# F73-M-V1_0.net
KiCad netlist of a schematic drawn in Altium Designer
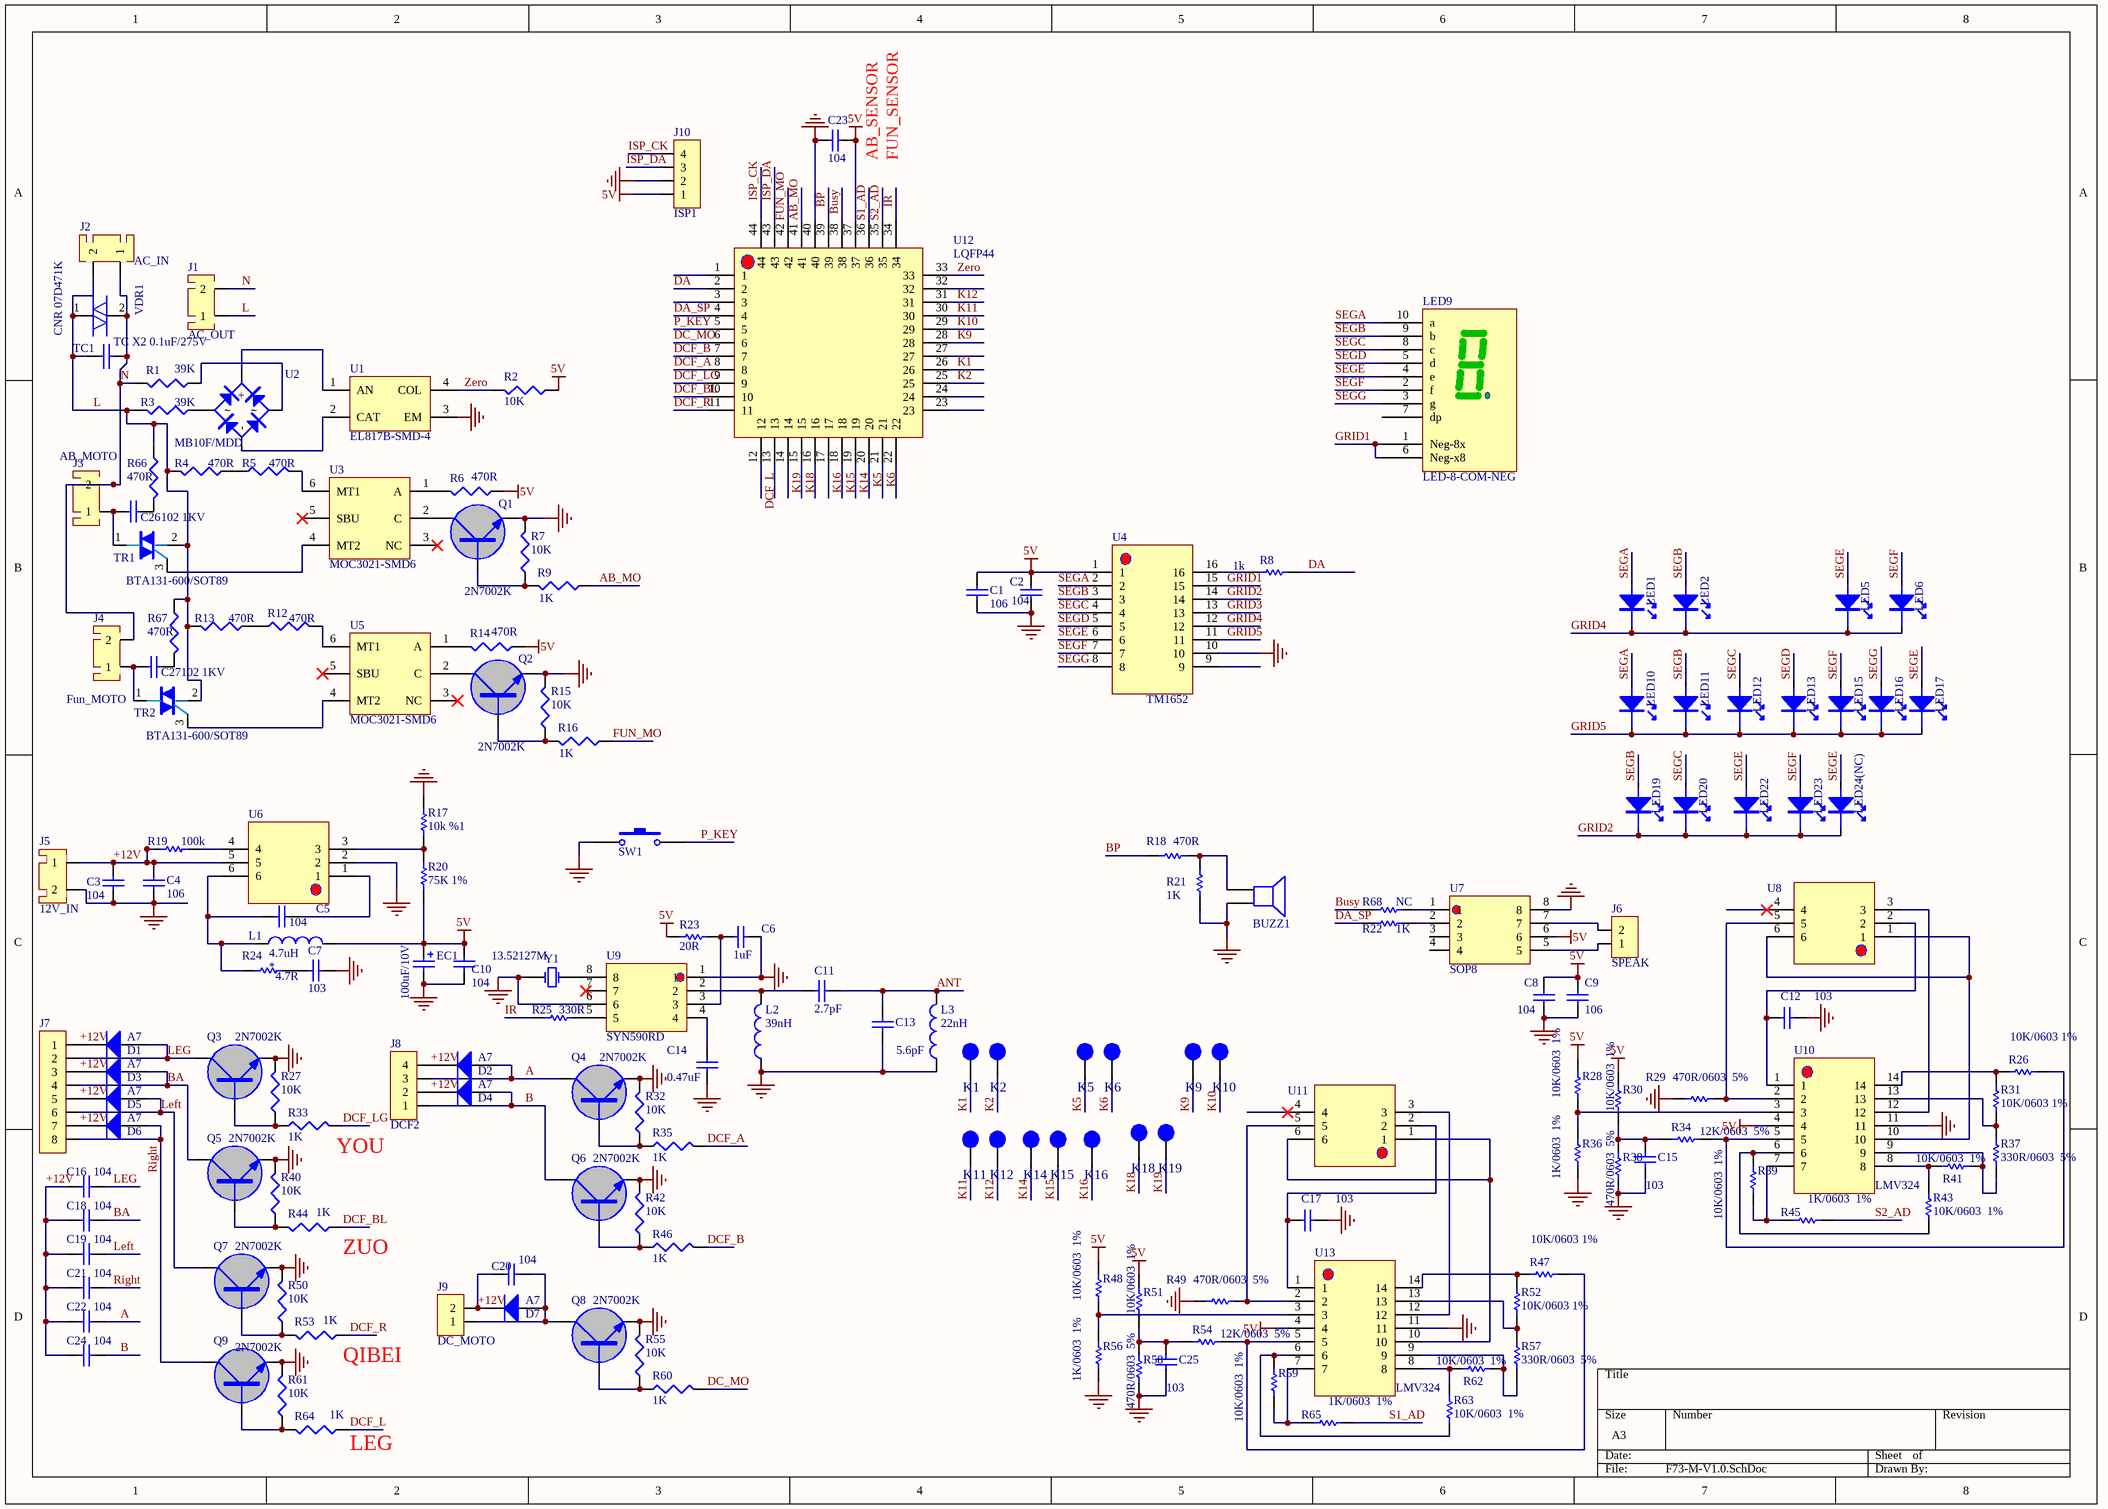
[diagram p0: F73-M-V1.0.SchDoc]

(export (version "E")
  (design (tool "Eeschema 10.0.6"))
  (components
    (comp (ref "BUZZ1")
      (value "Speaker")
      (footprint "BUZ-1407-7.5")
      (description "Loudspeaker")
      (fields (field (name "MANUFACTURER") "Generic Components"))
      (libsource (lib "Miscellaneous Devices") (part "Speaker"))
    )
    (comp (ref "C1")
      (value "106")
      (footprint "0805C")
      (description "Capacitor")
      (fields
        (field (name "MANUFACTURER") "Generic Components")
        (field (name "PUBLISHER") "Altium Hobart Technology Centre")
      )
      (libsource (lib "Miscellaneous Devices") (part "Cap"))
    )
    (comp (ref "C2")
      (value "104")
      (footprint "0603C")
      (description "Capacitor")
      (fields
        (field (name "MANUFACTURER") "Generic Components")
        (field (name "PUBLISHER") "Altium Hobart Technology Centre")
      )
      (libsource (lib "Miscellaneous Devices") (part "Cap"))
    )
    (comp (ref "C3")
      (value "104")
      (footprint "0603C")
      (description "Capacitor")
      (fields (field (name "PUBLISHER") "Altium Limited"))
      (libsource (lib "Phil") (part "Cap"))
    )
    (comp (ref "C4")
      (value "106")
      (footprint "0805C")
      (description "Capacitor")
      (fields
        (field (name "MANUFACTURER") "Generic Components")
        (field (name "PUBLISHER") "Altium Hobart Technology Centre")
      )
      (libsource (lib "Miscellaneous Devices") (part "Cap"))
    )
    (comp (ref "C5")
      (value "104")
      (footprint "0603C")
      (description "Capacitor")
      (fields
        (field (name "MANUFACTURER") "Generic Components")
        (field (name "PUBLISHER") "Altium Hobart Technology Centre")
      )
      (libsource (lib "Miscellaneous Devices") (part "Cap"))
    )
    (comp (ref "C6")
      (value "1uF")
      (footprint "0603C")
      (description "Capacitor")
      (fields (field (name "PUBLISHER") "Altium Limited"))
      (libsource (lib "Phil") (part "Cap"))
    )
    (comp (ref "C7")
      (value "103")
      (footprint "0603C")
      (description "Capacitor")
      (fields (field (name "PUBLISHER") "Altium Limited"))
      (libsource (lib "Phil") (part "Cap"))
    )
    (comp (ref "C8")
      (value "104")
      (footprint "0603C")
      (description "Capacitor")
      (fields
        (field (name "MANUFACTURER") "Generic Components")
        (field (name "PUBLISHER") "Altium Hobart Technology Centre")
      )
      (libsource (lib "Miscellaneous Devices") (part "Cap"))
    )
    (comp (ref "C9")
      (value "106")
      (footprint "0805C")
      (description "Capacitor")
      (fields
        (field (name "MANUFACTURER") "Generic Components")
        (field (name "PUBLISHER") "Altium Hobart Technology Centre")
      )
      (libsource (lib "Miscellaneous Devices") (part "Cap"))
    )
    (comp (ref "C10")
      (value "104")
      (footprint "0603C")
      (description "Capacitor")
      (fields
        (field (name "MANUFACTURER") "Generic Components")
        (field (name "PUBLISHER") "Altium Hobart Technology Centre")
      )
      (libsource (lib "Miscellaneous Devices") (part "Cap"))
    )
    (comp (ref "C11")
      (value "2.7pF")
      (footprint "0603C")
      (description "Capacitor")
      (fields (field (name "PUBLISHER") "Altium Limited"))
      (libsource (lib "Phil") (part "Cap"))
    )
    (comp (ref "C12")
      (value "103")
      (footprint "0603C")
      (description "Capacitor")
      (fields (field (name "PUBLISHER") "Altium Limited"))
      (libsource (lib "Phil") (part "Cap"))
    )
    (comp (ref "C13")
      (value "5.6pF")
      (footprint "0603C")
      (description "Capacitor")
      (fields (field (name "PUBLISHER") "Altium Limited"))
      (libsource (lib "Phil") (part "Cap"))
    )
    (comp (ref "C14")
      (value "0.47uF")
      (footprint "0603C")
      (description "Capacitor")
      (fields (field (name "PUBLISHER") "Altium Limited"))
      (libsource (lib "Phil") (part "Cap"))
    )
    (comp (ref "C15")
      (value "103")
      (footprint "0603C")
      (description "Capacitor")
      (fields (field (name "PUBLISHER") "Altium Limited"))
      (libsource (lib "Phil") (part "Cap"))
    )
    (comp (ref "C16")
      (value "104")
      (footprint "0603C")
      (description "Capacitor")
      (fields (field (name "PUBLISHER") "Altium Limited"))
      (libsource (lib "Phil") (part "Cap"))
    )
    (comp (ref "C17")
      (value "103")
      (footprint "0603C")
      (description "Capacitor")
      (fields (field (name "PUBLISHER") "Altium Limited"))
      (libsource (lib "Phil") (part "Cap"))
    )
    (comp (ref "C18")
      (value "104")
      (footprint "0603C")
      (description "Capacitor")
      (fields (field (name "PUBLISHER") "Altium Limited"))
      (libsource (lib "Phil") (part "Cap"))
    )
    (comp (ref "C19")
      (value "104")
      (footprint "0603C")
      (description "Capacitor")
      (fields (field (name "PUBLISHER") "Altium Limited"))
      (libsource (lib "Phil") (part "Cap"))
    )
    (comp (ref "C20")
      (value "104")
      (footprint "0603C")
      (description "Capacitor")
      (fields
        (field (name "MANUFACTURER") "Generic Components")
        (field (name "PUBLISHER") "Altium Hobart Technology Centre")
      )
      (libsource (lib "Miscellaneous Devices") (part "Cap"))
    )
    (comp (ref "C21")
      (value "104")
      (footprint "0603C")
      (description "Capacitor")
      (fields (field (name "PUBLISHER") "Altium Limited"))
      (libsource (lib "Phil") (part "Cap"))
    )
    (comp (ref "C22")
      (value "104")
      (footprint "0603C")
      (description "Capacitor")
      (fields (field (name "PUBLISHER") "Altium Limited"))
      (libsource (lib "Phil") (part "Cap"))
    )
    (comp (ref "C23")
      (value "104")
      (footprint "0603C")
      (description "Capacitor")
      (fields (field (name "PUBLISHER") "Altium Limited"))
      (libsource (lib "HF-FOUR-M-1.0") (part "Cap"))
    )
    (comp (ref "C24")
      (value "104")
      (footprint "0603C")
      (description "Capacitor")
      (fields (field (name "PUBLISHER") "Altium Limited"))
      (libsource (lib "Phil") (part "Cap"))
    )
    (comp (ref "C25")
      (value "103")
      (footprint "0603C")
      (description "Capacitor")
      (fields (field (name "PUBLISHER") "Altium Limited"))
      (libsource (lib "Phil") (part "Cap"))
    )
    (comp (ref "C26")
      (value "102 1KV")
      (footprint "1206C")
      (description "Capacitor")
      (fields
        (field (name "MANUFACTURER") "Generic Components")
        (field (name "PUBLISHER") "Altium Hobart Technology Centre")
      )
      (libsource (lib "Miscellaneous Devices") (part "Cap"))
    )
    (comp (ref "C27")
      (value "102 1KV")
      (footprint "1206C")
      (description "Capacitor")
      (fields
        (field (name "MANUFACTURER") "Generic Components")
        (field (name "PUBLISHER") "Altium Hobart Technology Centre")
      )
      (libsource (lib "Miscellaneous Devices") (part "Cap"))
    )
    (comp (ref "D1")
      (value "A7")
      (footprint "SOD-123FL_L2.8-W1.8-LS3.7")
      (description "1 Amp General Purpose Rectifier")
      (fields (field (name "PUBLISHER") "Altium Limited"))
      (libsource (lib "Phil") (part "Diode 1N4007"))
    )
    (comp (ref "D2")
      (value "A7")
      (footprint "SOD-123FL_L2.8-W1.8-LS3.7")
      (description "1 Amp General Purpose Rectifier")
      (fields (field (name "PUBLISHER") "Altium Limited"))
      (libsource (lib "Phil") (part "Diode 1N4007"))
    )
    (comp (ref "D3")
      (value "A7")
      (footprint "SOD-123FL_L2.8-W1.8-LS3.7")
      (description "1 Amp General Purpose Rectifier")
      (fields (field (name "PUBLISHER") "Altium Limited"))
      (libsource (lib "Phil") (part "Diode 1N4007"))
    )
    (comp (ref "D4")
      (value "A7")
      (footprint "SOD-123FL_L2.8-W1.8-LS3.7")
      (description "1 Amp General Purpose Rectifier")
      (fields (field (name "PUBLISHER") "Altium Limited"))
      (libsource (lib "Phil") (part "Diode 1N4007"))
    )
    (comp (ref "D5")
      (value "A7")
      (footprint "SOD-123FL_L2.8-W1.8-LS3.7")
      (description "1 Amp General Purpose Rectifier")
      (fields (field (name "PUBLISHER") "Altium Limited"))
      (libsource (lib "Phil") (part "Diode 1N4007"))
    )
    (comp (ref "D6")
      (value "A7")
      (footprint "SOD-123FL_L2.8-W1.8-LS3.7")
      (description "1 Amp General Purpose Rectifier")
      (fields (field (name "PUBLISHER") "Altium Limited"))
      (libsource (lib "Phil") (part "Diode 1N4007"))
    )
    (comp (ref "D7")
      (value "A7")
      (footprint "SOD-123FL_L2.8-W1.8-LS3.7")
      (description "1 Amp General Purpose Rectifier")
      (fields (field (name "PUBLISHER") "Altium Limited"))
      (libsource (lib "Phil") (part "Diode 1N4007"))
    )
    (comp (ref "EC1")
      (value "100uF/10V")
      (footprint "CAP SMD 6.3*5.5mm")
      (description "Polarized Capacitor (Radial)")
      (fields
        (field (name "MANUFACTURER") "Generic Components")
        (field (name "PUBLISHER") "Altium Hobart Technology Centre")
      )
      (libsource (lib "Miscellaneous Devices") (part "Cap Pol1"))
    )
    (comp (ref "J1")
      (value "AC_OUT")
      (footprint "K-VH3.96-3P")
      (libsource (lib "SCH Connector(2019-4-13)") (part "PITCH3.96-5.0-2A"))
    )
    (comp (ref "J2")
      (value "AC_IN")
      (footprint "K-VH3.96-3P")
      (libsource (lib "") (part "PITCH3.96-5.0-2A_1"))
    )
    (comp (ref "J3")
      (value "AB_MOTO")
      (footprint "K-VH3.96-3P")
      (libsource (lib "SCH Connector(2019-4-13)") (part "PITCH3.96-5.0-2A"))
    )
    (comp (ref "J4")
      (value "Fun_MOTO")
      (footprint "K-VH3.96-3P")
      (libsource (lib "SCH Connector(2019-4-13)") (part "PITCH3.96-5.0-2A"))
    )
    (comp (ref "J5")
      (value "12V_IN")
      (footprint "CON2-SMD-XHB 2*2.5MM")
      (libsource (lib "SCH Connector(2019-4-13)") (part "PITCH2.5-2A"))
    )
    (comp (ref "J6")
      (value "SPEAK")
      (footprint "CON2-SMD_PH2.0-1X2PW")
      (libsource (lib "Phil") (part "CON2"))
    )
    (comp (ref "J7")
      (value "~")
      (footprint "CON8-SMD-XHB 8*2.5MM")
      (libsource (lib "HF-FOUR-M-1.0") (part "CON8"))
    )
    (comp (ref "J8")
      (value "DCF2")
      (footprint "CON4-SMD_4P-P2.54_XH2.54-4AB")
      (libsource (lib "") (part "CON4_1"))
    )
    (comp (ref "J9")
      (value "DC_MOTO")
      (footprint "CON2-SMD-XHB 2*2.5MM")
      (libsource (lib "") (part "CON2_1"))
    )
    (comp (ref "J10") (value "ISP1") (footprint "CON4 -2.54-H") (libsource (lib "Phil") (part "CON4")))
    (comp (ref "K1")
      (value "Φ15 H8mm弹簧")
      (footprint "TK_HF-13*13*8")
      (libsource (lib "HF-FOUR-M-1.0") (part "TOUCH-PAD"))
    )
    (comp (ref "K2")
      (value "Φ15 H8mm弹簧")
      (footprint "TK_HF-13*13*8")
      (libsource (lib "HF-FOUR-M-1.0") (part "TOUCH-PAD"))
    )
    (comp (ref "K5")
      (value "Φ15 H8mm弹簧")
      (footprint "TK_HF-13*13*8")
      (libsource (lib "HF-FOUR-M-1.0") (part "TOUCH-PAD"))
    )
    (comp (ref "K6")
      (value "Φ15 H8mm弹簧")
      (footprint "TK_HF-13*13*8")
      (libsource (lib "HF-FOUR-M-1.0") (part "TOUCH-PAD"))
    )
    (comp (ref "K9")
      (value "Φ15 H8mm弹簧")
      (footprint "TK_HF-13*13*8")
      (libsource (lib "HF-FOUR-M-1.0") (part "TOUCH-PAD"))
    )
    (comp (ref "K10")
      (value "Φ15 H8mm弹簧")
      (footprint "TK_HF-13*13*8")
      (libsource (lib "HF-FOUR-M-1.0") (part "TOUCH-PAD"))
    )
    (comp (ref "K11")
      (value "Φ15 H8mm弹簧")
      (footprint "TK_HF-13*13*8")
      (libsource (lib "HF-FOUR-M-1.0") (part "TOUCH-PAD"))
    )
    (comp (ref "K12")
      (value "Φ15 H8mm弹簧")
      (footprint "TK_HF-13*13*8")
      (libsource (lib "HF-FOUR-M-1.0") (part "TOUCH-PAD"))
    )
    (comp (ref "K14")
      (value "Φ15 H8mm弹簧")
      (footprint "TK_HF-13*13*8")
      (libsource (lib "HF-FOUR-M-1.0") (part "TOUCH-PAD"))
    )
    (comp (ref "K15")
      (value "Φ15 H8mm弹簧")
      (footprint "TK_HF-13*13*8")
      (libsource (lib "HF-FOUR-M-1.0") (part "TOUCH-PAD"))
    )
    (comp (ref "K16")
      (value "Φ15 H8mm弹簧")
      (footprint "TK_HF-13*13*8")
      (libsource (lib "HF-FOUR-M-1.0") (part "TOUCH-PAD"))
    )
    (comp (ref "K18")
      (value "Φ15 H8mm弹簧")
      (footprint "TK_HF-13*13*8")
      (libsource (lib "HF-FOUR-M-1.0") (part "TOUCH-PAD"))
    )
    (comp (ref "K19")
      (value "Φ15 H8mm弹簧")
      (footprint "TK_HF-13*13*8")
      (libsource (lib "HF-FOUR-M-1.0") (part "TOUCH-PAD"))
    )
    (comp (ref "L1")
      (value "4.7uH")
      (footprint "INDC5050")
      (description "Inductor")
      (fields (field (name "ALTIUM_VALUE") "*") (field (name "PUBLISHER") "Altium Limited"))
      (libsource (lib "Phil") (part "Inductor"))
    )
    (comp (ref "L2")
      (value "39nH")
      (footprint "0603R")
      (description "Inductor")
      (fields (field (name "PUBLISHER") "Altium Limited"))
      (libsource (lib "Phil") (part "Inductor"))
    )
    (comp (ref "L3")
      (value "22nH")
      (footprint "0603R")
      (description "Inductor")
      (fields (field (name "PUBLISHER") "Altium Limited"))
      (libsource (lib "Phil") (part "Inductor"))
    )
    (comp (ref "LED1") (value "LED_0603") (footprint "LED_0603") (libsource (lib "Phil") (part "LED")))
    (comp (ref "LED2") (value "LED_0603") (footprint "LED_0603") (libsource (lib "Phil") (part "LED")))
    (comp (ref "LED5") (value "LED_0603") (footprint "LED_0603") (libsource (lib "Phil") (part "LED")))
    (comp (ref "LED6") (value "LED_0603") (footprint "LED_0603") (libsource (lib "Phil") (part "LED")))
    (comp (ref "LED9")
      (value "LED-8-COM-NEG")
      (footprint "LED1B-10P(7.5*14*H8.5 P2.54*10.16)")
      (libsource (lib "F73-M-V1.0") (part "LED-8-COM-NEG"))
    )
    (comp (ref "LED10") (value "LED_0603") (footprint "LED_0603") (libsource (lib "Phil") (part "LED")))
    (comp (ref "LED11") (value "LED_0603") (footprint "LED_0603") (libsource (lib "Phil") (part "LED")))
    (comp (ref "LED12") (value "LED_0603") (footprint "LED_0603") (libsource (lib "Phil") (part "LED")))
    (comp (ref "LED13") (value "LED_0603") (footprint "LED_0603") (libsource (lib "Phil") (part "LED")))
    (comp (ref "LED15") (value "LED_0603") (footprint "LED_0603") (libsource (lib "Phil") (part "LED")))
    (comp (ref "LED16") (value "LED_0603") (footprint "LED_0603") (libsource (lib "Phil") (part "LED")))
    (comp (ref "LED17") (value "LED_0603") (footprint "LED_0603") (libsource (lib "Phil") (part "LED")))
    (comp (ref "LED19") (value "LED_0603") (footprint "LED_0603") (libsource (lib "Phil") (part "LED")))
    (comp (ref "LED20") (value "LED_0603") (footprint "LED_0603") (libsource (lib "Phil") (part "LED")))
    (comp (ref "LED22") (value "LED_0603") (footprint "LED_0603") (libsource (lib "Phil") (part "LED")))
    (comp (ref "LED23") (value "LED_0603") (footprint "LED_0603") (libsource (lib "Phil") (part "LED")))
    (comp (ref "LED24(NC)") (value "LED_0603") (footprint "LED_0603") (libsource (lib "Phil") (part "LED")))
    (comp (ref "Q1")
      (value "2N7002K")
      (footprint "SOT-23 - MOS")
      (libsource (lib "SCH-Transistor-Triac-Mosfet(2018-9-19-1)") (part "NPN-8050-BCE-25V/500mA"))
    )
    (comp (ref "Q2")
      (value "2N7002K")
      (footprint "SOT-23 - MOS")
      (libsource (lib "SCH-Transistor-Triac-Mosfet(2018-9-19-1)") (part "NPN-8050-BCE-25V/500mA"))
    )
    (comp (ref "Q3")
      (value "2N7002K")
      (footprint "SOT-23 - MOS")
      (libsource (lib "SCH-Transistor-Triac-Mosfet(2018-9-19-1)") (part "NPN-8050-BCE-25V/500mA"))
    )
    (comp (ref "Q4")
      (value "2N7002K")
      (footprint "SOT-23 - MOS")
      (libsource (lib "SCH-Transistor-Triac-Mosfet(2018-9-19-1)") (part "NPN-8050-BCE-25V/500mA"))
    )
    (comp (ref "Q5")
      (value "2N7002K")
      (footprint "SOT-23 - MOS")
      (libsource (lib "SCH-Transistor-Triac-Mosfet(2018-9-19-1)") (part "NPN-8050-BCE-25V/500mA"))
    )
    (comp (ref "Q6")
      (value "2N7002K")
      (footprint "SOT-23 - MOS")
      (libsource (lib "SCH-Transistor-Triac-Mosfet(2018-9-19-1)") (part "NPN-8050-BCE-25V/500mA"))
    )
    (comp (ref "Q7")
      (value "2N7002K")
      (footprint "SOT-23 - MOS")
      (libsource (lib "SCH-Transistor-Triac-Mosfet(2018-9-19-1)") (part "NPN-8050-BCE-25V/500mA"))
    )
    (comp (ref "Q8")
      (value "2N7002K")
      (footprint "SOT-23 - MOS")
      (libsource (lib "SCH-Transistor-Triac-Mosfet(2018-9-19-1)") (part "NPN-8050-BCE-25V/500mA"))
    )
    (comp (ref "Q9")
      (value "2N7002K")
      (footprint "SOT-23 - MOS")
      (libsource (lib "SCH-Transistor-Triac-Mosfet(2018-9-19-1)") (part "NPN-8050-BCE-25V/500mA"))
    )
    (comp (ref "R1")
      (value "39K")
      (footprint "1206R")
      (libsource (lib "SCH Resistor(2019-6-10)") (part "1Ω±1%/0805-1206"))
    )
    (comp (ref "R2")
      (value "10K")
      (footprint "0603")
      (libsource (lib "SCH Resistor(2019-6-10)") (part "1Ω±1%/0603-0805"))
    )
    (comp (ref "R3")
      (value "39K")
      (footprint "1206R")
      (libsource (lib "SCH Resistor(2019-6-10)") (part "1Ω±1%/0805-1206"))
    )
    (comp (ref "R4")
      (value "470R")
      (footprint "1206R")
      (libsource (lib "SCH Resistor(2019-6-10)") (part "1Ω±1%/0805-1206"))
    )
    (comp (ref "R5")
      (value "470R")
      (footprint "1206R")
      (libsource (lib "SCH Resistor(2019-6-10)") (part "1Ω±1%/0805-1206"))
    )
    (comp (ref "R6")
      (value "470R")
      (footprint "0603")
      (libsource (lib "SCH Resistor(2019-6-10)") (part "1Ω±1%/0603-0805"))
    )
    (comp (ref "R7")
      (value "10K")
      (footprint "0603")
      (libsource (lib "SCH Resistor(2019-6-10)") (part "1Ω±1%/0603-0805"))
    )
    (comp (ref "R8")
      (value "1k")
      (footprint "0603R")
      (description "Resistor")
      (fields (field (name "PUBLISHER") "Altium Limited"))
      (libsource (lib "Phil") (part "Res1"))
    )
    (comp (ref "R9")
      (value "1K")
      (footprint "0603")
      (libsource (lib "SCH Resistor(2019-6-10)") (part "1Ω±1%/0603-0805"))
    )
    (comp (ref "R12")
      (value "470R")
      (footprint "1206R")
      (libsource (lib "SCH Resistor(2019-6-10)") (part "1Ω±1%/0805-1206"))
    )
    (comp (ref "R13")
      (value "470R")
      (footprint "1206R")
      (libsource (lib "SCH Resistor(2019-6-10)") (part "1Ω±1%/0805-1206"))
    )
    (comp (ref "R14")
      (value "470R")
      (footprint "0603")
      (libsource (lib "SCH Resistor(2019-6-10)") (part "1Ω±1%/0603-0805"))
    )
    (comp (ref "R15")
      (value "10K")
      (footprint "0603")
      (libsource (lib "SCH Resistor(2019-6-10)") (part "1Ω±1%/0603-0805"))
    )
    (comp (ref "R16")
      (value "1K")
      (footprint "0603")
      (libsource (lib "SCH Resistor(2019-6-10)") (part "1Ω±1%/0603-0805"))
    )
    (comp (ref "R17")
      (value "10k %1")
      (footprint "0603R")
      (description "Resistor")
      (fields (field (name "PUBLISHER") "Altium Limited"))
      (libsource (lib "Phil") (part "Res1"))
    )
    (comp (ref "R18")
      (value "470R")
      (footprint "0603R")
      (description "Resistor")
      (fields (field (name "PUBLISHER") "Altium Limited"))
      (libsource (lib "Phil") (part "Res1"))
    )
    (comp (ref "R19")
      (value "100k")
      (footprint "0603R")
      (description "Resistor")
      (fields (field (name "PUBLISHER") "Altium Limited"))
      (libsource (lib "Phil") (part "Res1"))
    )
    (comp (ref "R20")
      (value "75K 1%")
      (footprint "0603R")
      (description "Resistor")
      (fields (field (name "PUBLISHER") "Altium Limited"))
      (libsource (lib "Phil") (part "Res1"))
    )
    (comp (ref "R21")
      (value "1K")
      (footprint "0603R")
      (description "Resistor")
      (fields (field (name "PUBLISHER") "Altium Limited"))
      (libsource (lib "Phil") (part "Res1"))
    )
    (comp (ref "R22")
      (value "1K")
      (footprint "0603R")
      (description "Resistor")
      (fields (field (name "PUBLISHER") "Altium Limited"))
      (libsource (lib "Phil") (part "Res1"))
    )
    (comp (ref "R23")
      (value "20R")
      (footprint "0603R")
      (description "Resistor")
      (fields (field (name "PUBLISHER") "Altium Limited"))
      (libsource (lib "Phil") (part "Res1"))
    )
    (comp (ref "R24")
      (value "4.7R")
      (footprint "0603R")
      (description "Resistor")
      (fields (field (name "PUBLISHER") "Altium Limited"))
      (libsource (lib "Phil") (part "Res1"))
    )
    (comp (ref "R25")
      (value "330R")
      (footprint "0603R")
      (description "Resistor")
      (fields (field (name "PUBLISHER") "Altium Limited"))
      (libsource (lib "Phil") (part "Res1"))
    )
    (comp (ref "R26")
      (value "10K/0603 1%")
      (footprint "0603R")
      (description "Resistor")
      (fields (field (name "PUBLISHER") "Altium Limited"))
      (libsource (lib "Phil") (part "Res1"))
    )
    (comp (ref "R27")
      (value "10K")
      (footprint "0603")
      (libsource (lib "SCH Resistor(2019-6-10)") (part "1Ω±1%/0603-0805"))
    )
    (comp (ref "R28")
      (value "10K/0603  1%")
      (footprint "0603R")
      (description "Resistor")
      (fields (field (name "PUBLISHER") "Altium Limited"))
      (libsource (lib "Phil") (part "Res1"))
    )
    (comp (ref "R29")
      (value "470R/0603  5%")
      (footprint "0603R")
      (description "Resistor")
      (fields (field (name "PUBLISHER") "Altium Limited"))
      (libsource (lib "Phil") (part "Res1"))
    )
    (comp (ref "R30")
      (value "10K/0603  1%")
      (footprint "0603R")
      (description "Resistor")
      (fields (field (name "PUBLISHER") "Altium Limited"))
      (libsource (lib "Phil") (part "Res1"))
    )
    (comp (ref "R31")
      (value "10K/0603 1%")
      (footprint "0603R")
      (description "Resistor")
      (fields (field (name "PUBLISHER") "Altium Limited"))
      (libsource (lib "Phil") (part "Res1"))
    )
    (comp (ref "R32")
      (value "10K")
      (footprint "0603")
      (libsource (lib "SCH Resistor(2019-6-10)") (part "1Ω±1%/0603-0805"))
    )
    (comp (ref "R33")
      (value "1K")
      (footprint "0603")
      (libsource (lib "SCH Resistor(2019-6-10)") (part "1Ω±1%/0603-0805"))
    )
    (comp (ref "R34")
      (value "12K/0603  5%")
      (footprint "0603R")
      (description "Resistor")
      (fields (field (name "PUBLISHER") "Altium Limited"))
      (libsource (lib "Phil") (part "Res1"))
    )
    (comp (ref "R35")
      (value "1K")
      (footprint "0603")
      (libsource (lib "SCH Resistor(2019-6-10)") (part "1Ω±1%/0603-0805"))
    )
    (comp (ref "R36")
      (value "1K/0603  1%")
      (footprint "0603R")
      (description "Resistor")
      (fields (field (name "PUBLISHER") "Altium Limited"))
      (libsource (lib "Phil") (part "Res1"))
    )
    (comp (ref "R37")
      (value "330R/0603  5%")
      (footprint "0603R")
      (description "Resistor")
      (fields (field (name "PUBLISHER") "Altium Limited"))
      (libsource (lib "Phil") (part "Res1"))
    )
    (comp (ref "R38")
      (value "470R/0603  5%")
      (footprint "0603R")
      (description "Resistor")
      (fields (field (name "PUBLISHER") "Altium Limited"))
      (libsource (lib "Phil") (part "Res1"))
    )
    (comp (ref "R39")
      (value "10K/0603  1%")
      (footprint "0603R")
      (description "Resistor")
      (fields (field (name "PUBLISHER") "Altium Limited"))
      (libsource (lib "Phil") (part "Res1"))
    )
    (comp (ref "R40")
      (value "10K")
      (footprint "0603")
      (libsource (lib "SCH Resistor(2019-6-10)") (part "1Ω±1%/0603-0805"))
    )
    (comp (ref "R41")
      (value "10K/0603  1%")
      (footprint "0603R")
      (description "Resistor")
      (fields (field (name "PUBLISHER") "Altium Limited"))
      (libsource (lib "Phil") (part "Res1"))
    )
    (comp (ref "R42")
      (value "10K")
      (footprint "0603")
      (libsource (lib "SCH Resistor(2019-6-10)") (part "1Ω±1%/0603-0805"))
    )
    (comp (ref "R43")
      (value "10K/0603  1%")
      (footprint "0603R")
      (description "Resistor")
      (fields (field (name "PUBLISHER") "Altium Limited"))
      (libsource (lib "Phil") (part "Res1"))
    )
    (comp (ref "R44")
      (value "1K")
      (footprint "0603")
      (libsource (lib "SCH Resistor(2019-6-10)") (part "1Ω±1%/0603-0805"))
    )
    (comp (ref "R45")
      (value "1K/0603  1%")
      (footprint "0603R")
      (description "Resistor")
      (fields (field (name "PUBLISHER") "Altium Limited"))
      (libsource (lib "Phil") (part "Res1"))
    )
    (comp (ref "R46")
      (value "1K")
      (footprint "0603")
      (libsource (lib "SCH Resistor(2019-6-10)") (part "1Ω±1%/0603-0805"))
    )
    (comp (ref "R47")
      (value "10K/0603 1%")
      (footprint "0603R")
      (description "Resistor")
      (fields (field (name "PUBLISHER") "Altium Limited"))
      (libsource (lib "Phil") (part "Res1"))
    )
    (comp (ref "R48")
      (value "10K/0603  1%")
      (footprint "0603R")
      (description "Resistor")
      (fields (field (name "PUBLISHER") "Altium Limited"))
      (libsource (lib "Phil") (part "Res1"))
    )
    (comp (ref "R49")
      (value "470R/0603  5%")
      (footprint "0603R")
      (description "Resistor")
      (fields (field (name "PUBLISHER") "Altium Limited"))
      (libsource (lib "Phil") (part "Res1"))
    )
    (comp (ref "R50")
      (value "10K")
      (footprint "0603")
      (libsource (lib "SCH Resistor(2019-6-10)") (part "1Ω±1%/0603-0805"))
    )
    (comp (ref "R51")
      (value "10K/0603  1%")
      (footprint "0603R")
      (description "Resistor")
      (fields (field (name "PUBLISHER") "Altium Limited"))
      (libsource (lib "Phil") (part "Res1"))
    )
    (comp (ref "R52")
      (value "10K/0603 1%")
      (footprint "0603R")
      (description "Resistor")
      (fields (field (name "PUBLISHER") "Altium Limited"))
      (libsource (lib "Phil") (part "Res1"))
    )
    (comp (ref "R53")
      (value "1K")
      (footprint "0603")
      (libsource (lib "SCH Resistor(2019-6-10)") (part "1Ω±1%/0603-0805"))
    )
    (comp (ref "R54")
      (value "12K/0603  5%")
      (footprint "0603R")
      (description "Resistor")
      (fields (field (name "PUBLISHER") "Altium Limited"))
      (libsource (lib "Phil") (part "Res1"))
    )
    (comp (ref "R55")
      (value "10K")
      (footprint "0603")
      (libsource (lib "SCH Resistor(2019-6-10)") (part "1Ω±1%/0603-0805"))
    )
    (comp (ref "R56")
      (value "1K/0603  1%")
      (footprint "0603R")
      (description "Resistor")
      (fields (field (name "PUBLISHER") "Altium Limited"))
      (libsource (lib "Phil") (part "Res1"))
    )
    (comp (ref "R57")
      (value "330R/0603  5%")
      (footprint "0603R")
      (description "Resistor")
      (fields (field (name "PUBLISHER") "Altium Limited"))
      (libsource (lib "Phil") (part "Res1"))
    )
    (comp (ref "R58")
      (value "470R/0603  5%")
      (footprint "0603R")
      (description "Resistor")
      (fields (field (name "PUBLISHER") "Altium Limited"))
      (libsource (lib "Phil") (part "Res1"))
    )
    (comp (ref "R59")
      (value "10K/0603  1%")
      (footprint "0603R")
      (description "Resistor")
      (fields (field (name "PUBLISHER") "Altium Limited"))
      (libsource (lib "Phil") (part "Res1"))
    )
    (comp (ref "R60")
      (value "1K")
      (footprint "0603")
      (libsource (lib "SCH Resistor(2019-6-10)") (part "1Ω±1%/0603-0805"))
    )
    (comp (ref "R61")
      (value "10K")
      (footprint "0603")
      (libsource (lib "SCH Resistor(2019-6-10)") (part "1Ω±1%/0603-0805"))
    )
    (comp (ref "R62")
      (value "10K/0603  1%")
      (footprint "0603R")
      (description "Resistor")
      (fields (field (name "PUBLISHER") "Altium Limited"))
      (libsource (lib "Phil") (part "Res1"))
    )
    (comp (ref "R63")
      (value "10K/0603  1%")
      (footprint "0603R")
      (description "Resistor")
      (fields (field (name "PUBLISHER") "Altium Limited"))
      (libsource (lib "Phil") (part "Res1"))
    )
    (comp (ref "R64")
      (value "1K")
      (footprint "0603")
      (libsource (lib "SCH Resistor(2019-6-10)") (part "1Ω±1%/0603-0805"))
    )
    (comp (ref "R65")
      (value "1K/0603  1%")
      (footprint "0603R")
      (description "Resistor")
      (fields (field (name "PUBLISHER") "Altium Limited"))
      (libsource (lib "Phil") (part "Res1"))
    )
    (comp (ref "R66")
      (value "470R")
      (footprint "1206R")
      (libsource (lib "SCH Resistor(2019-6-10)") (part "1Ω±1%/0805-1206"))
    )
    (comp (ref "R67")
      (value "470R")
      (footprint "1206R")
      (libsource (lib "SCH Resistor(2019-6-10)") (part "1Ω±1%/0805-1206"))
    )
    (comp (ref "R68")
      (value "NC")
      (footprint "0603R")
      (description "Resistor")
      (fields (field (name "PUBLISHER") "Altium Limited"))
      (libsource (lib "Phil") (part "Res1"))
    )
    (comp (ref "SW1")
      (value "SW-PB")
      (footprint "BUTTON-SMD-6*6*10")
      (description "Switch")
      (fields (field (name "PUBLISHER") "Altium Limited"))
      (libsource (lib "Phil") (part "SW-PB"))
    )
    (comp (ref "TC1")
      (value "TC X2 0.1uF/275V")
      (footprint "CAP-TH_L13.0-W6.0-P10.00-D0.6")
      (libsource (lib "TEL SCH") (part "CAP1"))
    )
    (comp (ref "TR1")
      (value "BTA131-600/SOT89")
      (footprint "SOT-89 BT131-600")
      (libsource (lib "TEL SCH") (part "Triac"))
    )
    (comp (ref "TR2")
      (value "BTA131-600/SOT89")
      (footprint "SOT-89 BT131-600")
      (libsource (lib "TEL SCH") (part "Triac"))
    )
    (comp (ref "U1")
      (value "EL817B-SMD-4")
      (footprint "PC817-smd")
      (libsource (lib "SCH IC-Power(2019-2-14)") (part "EL817-DIP-4"))
    )
    (comp (ref "U2")
      (value "MB10F/MDD")
      (footprint "DB-MB10F")
      (description "Diode Bridge")
      (libsource (lib "SCH Diode-Bridge-Zener(2018-10-15)") (part "BD-ABS10/MB10S"))
    )
    (comp (ref "U3")
      (value "MOC3021-SMD6")
      (footprint "SMD6")
      (libsource (lib "SCH IC-Power(2019-2-14)") (part "MOC3021-DIP-6"))
    )
    (comp (ref "U4") (value "TM1652") (footprint "SOP16(150MIL)") (libsource (lib "Phil") (part "SOP16")))
    (comp (ref "U5")
      (value "MOC3021-SMD6")
      (footprint "SMD6")
      (libsource (lib "SCH IC-Power(2019-2-14)") (part "MOC3021-DIP-6"))
    )
    (comp (ref "U6") (value "HT7712") (footprint "SOT23-6_M") (libsource (lib "Phil") (part "SOP6")))
    (comp (ref "U7") (value "SOP8") (footprint "SOP8-SS") (libsource (lib "") (part "SOP8_1")))
    (comp (ref "U8") (value "SOP6") (footprint "PSG010R/S") (libsource (lib "Phil") (part "SOP6")))
    (comp (ref "U9") (value "SYN590RD") (footprint "SOP8(5.1*6.2mm)") (libsource (lib "Phil") (part "SOP8")))
    (comp (ref "U10") (value "LMV324") (footprint "SOP14(150mil)") (libsource (lib "Phil") (part "SOP14")))
    (comp (ref "U11") (value "SOP6") (footprint "PSG010R/S") (libsource (lib "Phil") (part "SOP6")))
    (comp (ref "U12") (value "LQFP44") (footprint "LQFP44") (libsource (lib "Phil") (part "LQFP44")))
    (comp (ref "U13") (value "LMV324") (footprint "SOP14(150mil)") (libsource (lib "Phil") (part "SOP14")))
    (comp (ref "VDR1")
      (value "CNR 07D471K")
      (footprint "RES-TH_L9.0-W5.0-P5-D0.7-S3.00")
      (libsource (lib "LZB_SCH") (part "VAR"))
    )
    (comp (ref "Y1")
      (value "13.52127M")
      (footprint "HC-49S_L11.4-W4.8")
      (description "Crystal Oscillator")
      (fields (field (name "PUBLISHER") "Altium Limited"))
      (libsource (lib "Phil") (part "XTAL"))
    )
  )
  (nets
    (net (code "1") (name "/+12V") (class "Default")
      (node (ref "C16") (pin "1") (pinfunction "1_1") (pintype "passive"))
      (node (ref "C18") (pin "1") (pinfunction "1_1") (pintype "passive"))
      (node (ref "C19") (pin "1") (pinfunction "1_1") (pintype "passive"))
      (node (ref "C20") (pin "1") (pinfunction "1_1") (pintype "passive"))
      (node (ref "C21") (pin "1") (pinfunction "1_1") (pintype "passive"))
      (node (ref "C22") (pin "1") (pinfunction "1_1") (pintype "passive"))
      (node (ref "C24") (pin "1") (pinfunction "1_1") (pintype "passive"))
      (node (ref "C3") (pin "1") (pinfunction "1_1") (pintype "passive"))
      (node (ref "C4") (pin "1") (pinfunction "1_1") (pintype "passive"))
      (node (ref "D1") (pin "2") (pinfunction "K_2") (pintype "passive"))
      (node (ref "D2") (pin "2") (pinfunction "K_2") (pintype "passive"))
      (node (ref "D3") (pin "2") (pinfunction "K_2") (pintype "passive"))
      (node (ref "D4") (pin "2") (pinfunction "K_2") (pintype "passive"))
      (node (ref "D5") (pin "2") (pinfunction "K_2") (pintype "passive"))
      (node (ref "D6") (pin "2") (pinfunction "K_2") (pintype "passive"))
      (node (ref "D7") (pin "2") (pinfunction "K_2") (pintype "passive"))
      (node (ref "J5") (pin "1") (pinfunction "1_1") (pintype "passive"))
      (node (ref "J7") (pin "1") (pinfunction "1_1") (pintype "passive"))
      (node (ref "J7") (pin "3") (pinfunction "3_3") (pintype "passive"))
      (node (ref "J7") (pin "5") (pinfunction "5_5") (pintype "passive"))
      (node (ref "J7") (pin "7") (pinfunction "7_7") (pintype "passive"))
      (node (ref "J8") (pin "2") (pinfunction "2_2") (pintype "passive"))
      (node (ref "J8") (pin "4") (pinfunction "4_4") (pintype "passive"))
      (node (ref "J9") (pin "2") (pinfunction "2_2") (pintype "passive"))
      (node (ref "R19") (pin "1") (pinfunction "1_1") (pintype "passive"))
      (node (ref "U6") (pin "5") (pinfunction "5_5") (pintype "passive"))
    )
    (net (code "2") (name "/A") (class "Default")
      (node (ref "C22") (pin "2") (pinfunction "2_2") (pintype "passive"))
      (node (ref "D2") (pin "1") (pinfunction "A_1") (pintype "passive"))
      (node (ref "J8") (pin "3") (pinfunction "3_3") (pintype "passive"))
      (node (ref "Q4") (pin "C") (pinfunction "C_C") (pintype "passive"))
    )
    (net (code "3") (name "/AB_MO") (class "Default")
      (node (ref "R9") (pin "1") (pintype "passive"))
      (node (ref "U12") (pin "41") (pinfunction "41_41") (pintype "passive"))
    )
    (net (code "4") (name "/ANT") (class "Default")
      (node (ref "C11") (pin "1") (pinfunction "1_1") (pintype "passive"))
      (node (ref "C13") (pin "2") (pinfunction "2_2") (pintype "passive"))
      (node (ref "L3") (pin "2") (pinfunction "2_2") (pintype "passive"))
    )
    (net (code "5") (name "/B") (class "Default")
      (node (ref "C24") (pin "2") (pinfunction "2_2") (pintype "passive"))
      (node (ref "D4") (pin "1") (pinfunction "A_1") (pintype "passive"))
      (node (ref "J8") (pin "1") (pinfunction "1_1") (pintype "passive"))
      (node (ref "Q6") (pin "C") (pinfunction "C_C") (pintype "passive"))
    )
    (net (code "6") (name "/BA") (class "Default")
      (node (ref "C18") (pin "2") (pinfunction "2_2") (pintype "passive"))
      (node (ref "D3") (pin "1") (pinfunction "A_1") (pintype "passive"))
      (node (ref "J7") (pin "4") (pinfunction "4_4") (pintype "passive"))
      (node (ref "Q5") (pin "C") (pinfunction "C_C") (pintype "passive"))
    )
    (net (code "7") (name "/BP") (class "Default")
      (node (ref "R18") (pin "2") (pinfunction "2_2") (pintype "passive"))
      (node (ref "U12") (pin "39") (pinfunction "39_39") (pintype "passive"))
    )
    (net (code "8") (name "/Busy") (class "Default")
      (node (ref "R68") (pin "1") (pinfunction "1_1") (pintype "passive"))
      (node (ref "U12") (pin "38") (pinfunction "38_38") (pintype "passive"))
    )
    (net (code "9") (name "/DA") (class "Default")
      (node (ref "R8") (pin "1") (pinfunction "1_1") (pintype "passive"))
      (node (ref "U12") (pin "2") (pinfunction "2_2") (pintype "passive"))
    )
    (net (code "10") (name "/DA_SP") (class "Default")
      (node (ref "R22") (pin "1") (pinfunction "1_1") (pintype "passive"))
      (node (ref "U12") (pin "4") (pinfunction "4_4") (pintype "passive"))
    )
    (net (code "11") (name "/DCF_A") (class "Default")
      (node (ref "R35") (pin "2") (pintype "passive"))
      (node (ref "U12") (pin "8") (pinfunction "8_8") (pintype "passive"))
    )
    (net (code "12") (name "/DCF_B") (class "Default")
      (node (ref "R46") (pin "2") (pintype "passive"))
      (node (ref "U12") (pin "7") (pinfunction "7_7") (pintype "passive"))
    )
    (net (code "13") (name "/DCF_BL") (class "Default")
      (node (ref "R44") (pin "1") (pintype "passive"))
      (node (ref "U12") (pin "10") (pinfunction "10_10") (pintype "passive"))
    )
    (net (code "14") (name "/DCF_L") (class "Default")
      (node (ref "R64") (pin "1") (pintype "passive"))
      (node (ref "U12") (pin "12") (pinfunction "12_12") (pintype "passive"))
    )
    (net (code "15") (name "/DCF_LG") (class "Default")
      (node (ref "R33") (pin "2") (pintype "passive"))
      (node (ref "U12") (pin "9") (pinfunction "9_9") (pintype "passive"))
    )
    (net (code "16") (name "/DCF_R") (class "Default")
      (node (ref "R53") (pin "1") (pintype "passive"))
      (node (ref "U12") (pin "11") (pinfunction "11_11") (pintype "passive"))
    )
    (net (code "17") (name "/DC_MO") (class "Default")
      (node (ref "R60") (pin "2") (pintype "passive"))
      (node (ref "U12") (pin "6") (pinfunction "6_6") (pintype "passive"))
    )
    (net (code "18") (name "/FUN_MO") (class "Default")
      (node (ref "R16") (pin "1") (pintype "passive"))
      (node (ref "U12") (pin "42") (pinfunction "42_42") (pintype "passive"))
    )
    (net (code "19") (name "/GRID1") (class "Default")
      (node (ref "LED9") (pin "1") (pinfunction "Neg-8x_1") (pintype "passive"))
      (node (ref "LED9") (pin "6") (pinfunction "Neg-x8_6") (pintype "passive"))
      (node (ref "U4") (pin "15") (pinfunction "15_15") (pintype "passive"))
    )
    (net (code "20") (name "/GRID2") (class "Default")
      (node (ref "LED19") (pin "2") (pinfunction "2_2") (pintype "passive"))
      (node (ref "LED20") (pin "2") (pinfunction "2_2") (pintype "passive"))
      (node (ref "LED22") (pin "2") (pinfunction "2_2") (pintype "passive"))
      (node (ref "LED23") (pin "2") (pinfunction "2_2") (pintype "passive"))
      (node (ref "LED24(NC)") (pin "2") (pinfunction "2_2") (pintype "passive"))
      (node (ref "U4") (pin "14") (pinfunction "14_14") (pintype "passive"))
    )
    (net (code "21") (name "/GRID3") (class "Default")
      (node (ref "U4") (pin "13") (pinfunction "13_13") (pintype "passive"))
    )
    (net (code "22") (name "/GRID4") (class "Default")
      (node (ref "LED1") (pin "2") (pinfunction "2_2") (pintype "passive"))
      (node (ref "LED2") (pin "2") (pinfunction "2_2") (pintype "passive"))
      (node (ref "LED5") (pin "2") (pinfunction "2_2") (pintype "passive"))
      (node (ref "LED6") (pin "2") (pinfunction "2_2") (pintype "passive"))
      (node (ref "U4") (pin "12") (pinfunction "12_12") (pintype "passive"))
    )
    (net (code "23") (name "/GRID5") (class "Default")
      (node (ref "LED10") (pin "2") (pinfunction "2_2") (pintype "passive"))
      (node (ref "LED11") (pin "2") (pinfunction "2_2") (pintype "passive"))
      (node (ref "LED12") (pin "2") (pinfunction "2_2") (pintype "passive"))
      (node (ref "LED13") (pin "2") (pinfunction "2_2") (pintype "passive"))
      (node (ref "LED15") (pin "2") (pinfunction "2_2") (pintype "passive"))
      (node (ref "LED16") (pin "2") (pinfunction "2_2") (pintype "passive"))
      (node (ref "LED17") (pin "2") (pinfunction "2_2") (pintype "passive"))
      (node (ref "U4") (pin "11") (pinfunction "11_11") (pintype "passive"))
    )
    (net (code "24") (name "/IR") (class "Default")
      (node (ref "R25") (pin "1") (pinfunction "1_1") (pintype "passive"))
      (node (ref "U12") (pin "34") (pinfunction "34_34") (pintype "passive"))
    )
    (net (code "25") (name "/ISP_CK") (class "Default")
      (node (ref "J10") (pin "4") (pinfunction "4_4") (pintype "passive"))
      (node (ref "U12") (pin "44") (pinfunction "44_44") (pintype "passive"))
    )
    (net (code "26") (name "/ISP_DA") (class "Default")
      (node (ref "J10") (pin "3") (pinfunction "3_3") (pintype "passive"))
      (node (ref "U12") (pin "43") (pinfunction "43_43") (pintype "passive"))
    )
    (net (code "27") (name "/K1") (class "Default")
      (node (ref "K1") (pin "2") (pinfunction "2_2") (pintype "passive"))
      (node (ref "U12") (pin "26") (pinfunction "26_26") (pintype "passive"))
    )
    (net (code "28") (name "/K2") (class "Default")
      (node (ref "K2") (pin "2") (pinfunction "2_2") (pintype "passive"))
      (node (ref "U12") (pin "25") (pinfunction "25_25") (pintype "passive"))
    )
    (net (code "29") (name "/K5") (class "Default")
      (node (ref "K5") (pin "2") (pinfunction "2_2") (pintype "passive"))
      (node (ref "U12") (pin "20") (pinfunction "20_20") (pintype "passive"))
    )
    (net (code "30") (name "/K6") (class "Default")
      (node (ref "K6") (pin "2") (pinfunction "2_2") (pintype "passive"))
      (node (ref "U12") (pin "21") (pinfunction "21_21") (pintype "passive"))
    )
    (net (code "31") (name "/K9") (class "Default")
      (node (ref "K9") (pin "2") (pinfunction "2_2") (pintype "passive"))
      (node (ref "U12") (pin "28") (pinfunction "28_28") (pintype "passive"))
    )
    (net (code "32") (name "/K10") (class "Default")
      (node (ref "K10") (pin "2") (pinfunction "2_2") (pintype "passive"))
      (node (ref "U12") (pin "29") (pinfunction "29_29") (pintype "passive"))
    )
    (net (code "33") (name "/K11") (class "Default")
      (node (ref "K11") (pin "2") (pinfunction "2_2") (pintype "passive"))
      (node (ref "U12") (pin "30") (pinfunction "30_30") (pintype "passive"))
    )
    (net (code "34") (name "/K12") (class "Default")
      (node (ref "K12") (pin "2") (pinfunction "2_2") (pintype "passive"))
      (node (ref "U12") (pin "31") (pinfunction "31_31") (pintype "passive"))
    )
    (net (code "35") (name "/K14") (class "Default")
      (node (ref "K14") (pin "2") (pinfunction "2_2") (pintype "passive"))
      (node (ref "U12") (pin "19") (pinfunction "19_19") (pintype "passive"))
    )
    (net (code "36") (name "/K15") (class "Default")
      (node (ref "K15") (pin "2") (pinfunction "2_2") (pintype "passive"))
      (node (ref "U12") (pin "18") (pinfunction "18_18") (pintype "passive"))
    )
    (net (code "37") (name "/K16") (class "Default")
      (node (ref "K16") (pin "2") (pinfunction "2_2") (pintype "passive"))
      (node (ref "U12") (pin "17") (pinfunction "17_17") (pintype "passive"))
    )
    (net (code "38") (name "/K18") (class "Default")
      (node (ref "K18") (pin "2") (pinfunction "2_2") (pintype "passive"))
      (node (ref "U12") (pin "15") (pinfunction "15_15") (pintype "passive"))
    )
    (net (code "39") (name "/K19") (class "Default")
      (node (ref "K19") (pin "2") (pinfunction "2_2") (pintype "passive"))
      (node (ref "U12") (pin "14") (pinfunction "14_14") (pintype "passive"))
    )
    (net (code "40") (name "/L") (class "Default")
      (node (ref "J1") (pin "1") (pinfunction "1_1") (pintype "passive"))
      (node (ref "J2") (pin "2") (pinfunction "2_2") (pintype "passive"))
      (node (ref "R13") (pin "2") (pintype "passive"))
      (node (ref "R3") (pin "2") (pintype "passive"))
      (node (ref "R4") (pin "2") (pintype "passive"))
      (node (ref "R66") (pin "1") (pintype "passive"))
      (node (ref "R67") (pin "1") (pintype "passive"))
      (node (ref "TC1") (pin "2") (pintype "passive"))
      (node (ref "TR1") (pin "2") (pintype "passive"))
      (node (ref "TR2") (pin "2") (pintype "passive"))
      (node (ref "VDR1") (pin "1") (pinfunction "1_1") (pintype "passive"))
    )
    (net (code "41") (name "/LEG") (class "Default")
      (node (ref "C16") (pin "2") (pinfunction "2_2") (pintype "passive"))
      (node (ref "D1") (pin "1") (pinfunction "A_1") (pintype "passive"))
      (node (ref "J7") (pin "2") (pinfunction "2_2") (pintype "passive"))
      (node (ref "Q3") (pin "C") (pinfunction "C_C") (pintype "passive"))
    )
    (net (code "42") (name "/Left") (class "Default")
      (node (ref "C19") (pin "2") (pinfunction "2_2") (pintype "passive"))
      (node (ref "D5") (pin "1") (pinfunction "A_1") (pintype "passive"))
      (node (ref "J7") (pin "6") (pinfunction "6_6") (pintype "passive"))
      (node (ref "Q7") (pin "C") (pinfunction "C_C") (pintype "passive"))
    )
    (net (code "43") (name "/N") (class "Default")
      (node (ref "J1") (pin "2") (pinfunction "2_2") (pintype "passive"))
      (node (ref "J2") (pin "1") (pinfunction "1_1") (pintype "passive"))
      (node (ref "J3") (pin "2") (pinfunction "2_2") (pintype "passive"))
      (node (ref "J4") (pin "2") (pinfunction "2_2") (pintype "passive"))
      (node (ref "R1") (pin "2") (pintype "passive"))
      (node (ref "TC1") (pin "1") (pintype "passive"))
      (node (ref "VDR1") (pin "2") (pinfunction "2_2") (pintype "passive"))
    )
    (net (code "44") (name "/P_KEY") (class "Default")
      (node (ref "SW1") (pin "2") (pinfunction "2_2") (pintype "passive"))
      (node (ref "U12") (pin "5") (pinfunction "5_5") (pintype "passive"))
    )
    (net (code "45") (name "/Right") (class "Default")
      (node (ref "C21") (pin "2") (pinfunction "2_2") (pintype "passive"))
      (node (ref "D6") (pin "1") (pinfunction "A_1") (pintype "passive"))
      (node (ref "J7") (pin "8") (pinfunction "8_8") (pintype "passive"))
      (node (ref "Q9") (pin "C") (pinfunction "C_C") (pintype "passive"))
    )
    (net (code "46") (name "/S1_AD") (class "Default")
      (node (ref "R65") (pin "1") (pinfunction "1_1") (pintype "passive"))
      (node (ref "U12") (pin "36") (pinfunction "36_36") (pintype "passive"))
    )
    (net (code "47") (name "/S2_AD") (class "Default")
      (node (ref "R45") (pin "1") (pinfunction "1_1") (pintype "passive"))
      (node (ref "U12") (pin "35") (pinfunction "35_35") (pintype "passive"))
    )
    (net (code "48") (name "/SEGA") (class "Default")
      (node (ref "LED1") (pin "1") (pinfunction "1_1") (pintype "passive"))
      (node (ref "LED10") (pin "1") (pinfunction "1_1") (pintype "passive"))
      (node (ref "LED9") (pin "10") (pinfunction "a_10") (pintype "passive"))
      (node (ref "U4") (pin "2") (pinfunction "2_2") (pintype "passive"))
    )
    (net (code "49") (name "/SEGB") (class "Default")
      (node (ref "LED11") (pin "1") (pinfunction "1_1") (pintype "passive"))
      (node (ref "LED19") (pin "1") (pinfunction "1_1") (pintype "passive"))
      (node (ref "LED2") (pin "1") (pinfunction "1_1") (pintype "passive"))
      (node (ref "LED9") (pin "9") (pinfunction "b_9") (pintype "passive"))
      (node (ref "U4") (pin "3") (pinfunction "3_3") (pintype "passive"))
    )
    (net (code "50") (name "/SEGC") (class "Default")
      (node (ref "LED12") (pin "1") (pinfunction "1_1") (pintype "passive"))
      (node (ref "LED20") (pin "1") (pinfunction "1_1") (pintype "passive"))
      (node (ref "LED9") (pin "8") (pinfunction "c_8") (pintype "passive"))
      (node (ref "U4") (pin "4") (pinfunction "4_4") (pintype "passive"))
    )
    (net (code "51") (name "/SEGD") (class "Default")
      (node (ref "LED13") (pin "1") (pinfunction "1_1") (pintype "passive"))
      (node (ref "LED9") (pin "5") (pinfunction "d_5") (pintype "passive"))
      (node (ref "U4") (pin "5") (pinfunction "5_5") (pintype "passive"))
    )
    (net (code "52") (name "/SEGE") (class "Default")
      (node (ref "LED17") (pin "1") (pinfunction "1_1") (pintype "passive"))
      (node (ref "LED22") (pin "1") (pinfunction "1_1") (pintype "passive"))
      (node (ref "LED24(NC)") (pin "1") (pinfunction "1_1") (pintype "passive"))
      (node (ref "LED5") (pin "1") (pinfunction "1_1") (pintype "passive"))
      (node (ref "LED9") (pin "4") (pinfunction "e_4") (pintype "passive"))
      (node (ref "U4") (pin "6") (pinfunction "6_6") (pintype "passive"))
    )
    (net (code "53") (name "/SEGF") (class "Default")
      (node (ref "LED15") (pin "1") (pinfunction "1_1") (pintype "passive"))
      (node (ref "LED23") (pin "1") (pinfunction "1_1") (pintype "passive"))
      (node (ref "LED6") (pin "1") (pinfunction "1_1") (pintype "passive"))
      (node (ref "LED9") (pin "2") (pinfunction "f_2") (pintype "passive"))
      (node (ref "U4") (pin "7") (pinfunction "7_7") (pintype "passive"))
    )
    (net (code "54") (name "/SEGG") (class "Default")
      (node (ref "LED16") (pin "1") (pinfunction "1_1") (pintype "passive"))
      (node (ref "LED9") (pin "3") (pinfunction "g_3") (pintype "passive"))
      (node (ref "U4") (pin "8") (pinfunction "8_8") (pintype "passive"))
    )
    (net (code "55") (name "/Zero") (class "Default")
      (node (ref "R2") (pin "2") (pintype "passive"))
      (node (ref "U1") (pin "4") (pinfunction "COL_4") (pintype "passive"))
      (node (ref "U12") (pin "33") (pinfunction "33_33") (pintype "passive"))
    )
    (net (code "56") (name "5V") (class "Default")
      (node (ref "C1") (pin "2") (pinfunction "2_2") (pintype "passive"))
      (node (ref "C10") (pin "1") (pinfunction "1_1") (pintype "passive"))
      (node (ref "C2") (pin "2") (pinfunction "2_2") (pintype "passive"))
      (node (ref "C23") (pin "1") (pinfunction "1_1") (pintype "passive"))
      (node (ref "C8") (pin "1") (pinfunction "1_1") (pintype "passive"))
      (node (ref "C9") (pin "1") (pinfunction "1_1") (pintype "passive"))
      (node (ref "EC1") (pin "1") (pinfunction "1_1") (pintype "passive"))
      (node (ref "J10") (pin "1") (pinfunction "1_1") (pintype "passive"))
      (node (ref "L1") (pin "2") (pinfunction "2_2") (pintype "passive"))
      (node (ref "R14") (pin "1") (pintype "passive"))
      (node (ref "R2") (pin "1") (pintype "passive"))
      (node (ref "R20") (pin "1") (pinfunction "1_1") (pintype "passive"))
      (node (ref "R23") (pin "1") (pinfunction "1_1") (pintype "passive"))
      (node (ref "R28") (pin "1") (pinfunction "1_1") (pintype "passive"))
      (node (ref "R30") (pin "1") (pinfunction "1_1") (pintype "passive"))
      (node (ref "R48") (pin "1") (pinfunction "1_1") (pintype "passive"))
      (node (ref "R51") (pin "1") (pinfunction "1_1") (pintype "passive"))
      (node (ref "R6") (pin "1") (pintype "passive"))
      (node (ref "U10") (pin "4") (pinfunction "4_4") (pintype "passive"))
      (node (ref "U12") (pin "37") (pinfunction "37_37") (pintype "passive"))
      (node (ref "U13") (pin "4") (pinfunction "4_4") (pintype "passive"))
      (node (ref "U4") (pin "1") (pinfunction "1_1") (pintype "passive"))
      (node (ref "U7") (pin "6") (pinfunction "6_6") (pintype "passive"))
    )
    (net (code "57") (name "GND") (class "Default")
      (node (ref "BUZZ1") (pin "1") (pinfunction "1_1") (pintype "passive"))
      (node (ref "C1") (pin "1") (pinfunction "1_1") (pintype "passive"))
      (node (ref "C10") (pin "2") (pinfunction "2_2") (pintype "passive"))
      (node (ref "C12") (pin "1") (pinfunction "1_1") (pintype "passive"))
      (node (ref "C13") (pin "1") (pinfunction "1_1") (pintype "passive"))
      (node (ref "C14") (pin "2") (pinfunction "2_2") (pintype "passive"))
      (node (ref "C15") (pin "1") (pinfunction "1_1") (pintype "passive"))
      (node (ref "C17") (pin "1") (pinfunction "1_1") (pintype "passive"))
      (node (ref "C2") (pin "1") (pinfunction "1_1") (pintype "passive"))
      (node (ref "C23") (pin "2") (pinfunction "2_2") (pintype "passive"))
      (node (ref "C25") (pin "1") (pinfunction "1_1") (pintype "passive"))
      (node (ref "C3") (pin "2") (pinfunction "2_2") (pintype "passive"))
      (node (ref "C4") (pin "2") (pinfunction "2_2") (pintype "passive"))
      (node (ref "C6") (pin "2") (pinfunction "2_2") (pintype "passive"))
      (node (ref "C7") (pin "1") (pinfunction "1_1") (pintype "passive"))
      (node (ref "C8") (pin "2") (pinfunction "2_2") (pintype "passive"))
      (node (ref "C9") (pin "2") (pinfunction "2_2") (pintype "passive"))
      (node (ref "EC1") (pin "2") (pinfunction "2_2") (pintype "passive"))
      (node (ref "J10") (pin "2") (pinfunction "2_2") (pintype "passive"))
      (node (ref "J5") (pin "2") (pinfunction "2_2") (pintype "passive"))
      (node (ref "L2") (pin "1") (pinfunction "1_1") (pintype "passive"))
      (node (ref "L3") (pin "1") (pinfunction "1_1") (pintype "passive"))
      (node (ref "Q1") (pin "E") (pinfunction "E_E") (pintype "passive"))
      (node (ref "Q2") (pin "E") (pinfunction "E_E") (pintype "passive"))
      (node (ref "Q3") (pin "E") (pinfunction "E_E") (pintype "passive"))
      (node (ref "Q4") (pin "E") (pinfunction "E_E") (pintype "passive"))
      (node (ref "Q5") (pin "E") (pinfunction "E_E") (pintype "passive"))
      (node (ref "Q6") (pin "E") (pinfunction "E_E") (pintype "passive"))
      (node (ref "Q7") (pin "E") (pinfunction "E_E") (pintype "passive"))
      (node (ref "Q8") (pin "E") (pinfunction "E_E") (pintype "passive"))
      (node (ref "Q9") (pin "E") (pinfunction "E_E") (pintype "passive"))
      (node (ref "R15") (pin "2") (pintype "passive"))
      (node (ref "R17") (pin "2") (pinfunction "2_2") (pintype "passive"))
      (node (ref "R21") (pin "2") (pinfunction "2_2") (pintype "passive"))
      (node (ref "R27") (pin "2") (pintype "passive"))
      (node (ref "R29") (pin "2") (pinfunction "2_2") (pintype "passive"))
      (node (ref "R32") (pin "2") (pintype "passive"))
      (node (ref "R36") (pin "2") (pinfunction "2_2") (pintype "passive"))
      (node (ref "R38") (pin "2") (pinfunction "2_2") (pintype "passive"))
      (node (ref "R40") (pin "2") (pintype "passive"))
      (node (ref "R42") (pin "2") (pintype "passive"))
      (node (ref "R49") (pin "2") (pinfunction "2_2") (pintype "passive"))
      (node (ref "R50") (pin "2") (pintype "passive"))
      (node (ref "R55") (pin "2") (pintype "passive"))
      (node (ref "R56") (pin "2") (pinfunction "2_2") (pintype "passive"))
      (node (ref "R58") (pin "2") (pinfunction "2_2") (pintype "passive"))
      (node (ref "R61") (pin "2") (pintype "passive"))
      (node (ref "R7") (pin "2") (pintype "passive"))
      (node (ref "SW1") (pin "1") (pinfunction "1_1") (pintype "passive"))
      (node (ref "U1") (pin "3") (pinfunction "EM_3") (pintype "passive"))
      (node (ref "U10") (pin "11") (pinfunction "11_11") (pintype "passive"))
      (node (ref "U12") (pin "40") (pinfunction "40_40") (pintype "passive"))
      (node (ref "U13") (pin "11") (pinfunction "11_11") (pintype "passive"))
      (node (ref "U4") (pin "10") (pinfunction "10_10") (pintype "passive"))
      (node (ref "U6") (pin "2") (pinfunction "2_2") (pintype "passive"))
      (node (ref "U7") (pin "8") (pinfunction "8_8") (pintype "passive"))
      (node (ref "U9") (pin "1") (pinfunction "1_1") (pintype "passive"))
      (node (ref "U9") (pin "6") (pinfunction "6_6") (pintype "passive"))
      (node (ref "Y1") (pin "2") (pinfunction "OSC2_2") (pintype "passive"))
    )
    (net (code "58") (name "Net-(BUZZ1-Pad2)") (class "Default")
      (node (ref "BUZZ1") (pin "2") (pinfunction "2_2") (pintype "passive"))
      (node (ref "R18") (pin "1") (pinfunction "1_1") (pintype "passive"))
      (node (ref "R21") (pin "1") (pinfunction "1_1") (pintype "passive"))
    )
    (net (code "59") (name "Net-(C5-Pad1)") (class "Default")
      (node (ref "C5") (pin "1") (pinfunction "1_1") (pintype "passive"))
      (node (ref "U6") (pin "1") (pinfunction "1_1") (pintype "passive"))
    )
    (net (code "60") (name "Net-(C5-Pad2)") (class "Default")
      (node (ref "C5") (pin "2") (pinfunction "2_2") (pintype "passive"))
      (node (ref "L1") (pin "1") (pinfunction "1_1") (pintype "passive"))
      (node (ref "R24") (pin "2") (pinfunction "2_2") (pintype "passive"))
      (node (ref "U6") (pin "6") (pinfunction "6_6") (pintype "passive"))
    )
    (net (code "61") (name "Net-(C6-Pad1)") (class "Default")
      (node (ref "C6") (pin "1") (pinfunction "1_1") (pintype "passive"))
      (node (ref "R23") (pin "2") (pinfunction "2_2") (pintype "passive"))
      (node (ref "U9") (pin "3") (pinfunction "3_3") (pintype "passive"))
    )
    (net (code "62") (name "Net-(C7-Pad2)") (class "Default")
      (node (ref "C7") (pin "2") (pinfunction "2_2") (pintype "passive"))
      (node (ref "R24") (pin "1") (pinfunction "1_1") (pintype "passive"))
    )
    (net (code "63") (name "Net-(C11-Pad2)") (class "Default")
      (node (ref "C11") (pin "2") (pinfunction "2_2") (pintype "passive"))
      (node (ref "L2") (pin "2") (pinfunction "2_2") (pintype "passive"))
      (node (ref "U9") (pin "2") (pinfunction "2_2") (pintype "passive"))
    )
    (net (code "64") (name "Net-(C12-Pad2)") (class "Default")
      (node (ref "C12") (pin "2") (pinfunction "2_2") (pintype "passive"))
      (node (ref "U10") (pin "1") (pinfunction "1_1") (pintype "passive"))
      (node (ref "U8") (pin "2") (pinfunction "2_2") (pintype "passive"))
    )
    (net (code "65") (name "Net-(C14-Pad1)") (class "Default")
      (node (ref "C14") (pin "1") (pinfunction "1_1") (pintype "passive"))
      (node (ref "U9") (pin "4") (pinfunction "4_4") (pintype "passive"))
    )
    (net (code "66") (name "Net-(C15-Pad2)") (class "Default")
      (node (ref "C15") (pin "2") (pinfunction "2_2") (pintype "passive"))
      (node (ref "R30") (pin "2") (pinfunction "2_2") (pintype "passive"))
      (node (ref "R34") (pin "2") (pinfunction "2_2") (pintype "passive"))
      (node (ref "R38") (pin "1") (pinfunction "1_1") (pintype "passive"))
    )
    (net (code "67") (name "Net-(C17-Pad2)") (class "Default")
      (node (ref "C17") (pin "2") (pinfunction "2_2") (pintype "passive"))
      (node (ref "U11") (pin "2") (pinfunction "2_2") (pintype "passive"))
      (node (ref "U13") (pin "1") (pinfunction "1_1") (pintype "passive"))
    )
    (net (code "68") (name "Net-(C25-Pad2)") (class "Default")
      (node (ref "C25") (pin "2") (pinfunction "2_2") (pintype "passive"))
      (node (ref "R51") (pin "2") (pinfunction "2_2") (pintype "passive"))
      (node (ref "R54") (pin "2") (pinfunction "2_2") (pintype "passive"))
      (node (ref "R58") (pin "1") (pinfunction "1_1") (pintype "passive"))
    )
    (net (code "69") (name "Net-(C26-Pad1)") (class "Default")
      (node (ref "C26") (pin "1") (pinfunction "1_1") (pintype "passive"))
      (node (ref "R66") (pin "2") (pintype "passive"))
    )
    (net (code "70") (name "Net-(C26-Pad2)") (class "Default")
      (node (ref "C26") (pin "2") (pinfunction "2_2") (pintype "passive"))
      (node (ref "J3") (pin "1") (pinfunction "1_1") (pintype "passive"))
      (node (ref "TR1") (pin "1") (pintype "passive"))
    )
    (net (code "71") (name "Net-(C27-Pad1)") (class "Default")
      (node (ref "C27") (pin "1") (pinfunction "1_1") (pintype "passive"))
      (node (ref "R67") (pin "2") (pintype "passive"))
    )
    (net (code "72") (name "Net-(C27-Pad2)") (class "Default")
      (node (ref "C27") (pin "2") (pinfunction "2_2") (pintype "passive"))
      (node (ref "J4") (pin "1") (pinfunction "1_1") (pintype "passive"))
      (node (ref "TR2") (pin "1") (pintype "passive"))
    )
    (net (code "73") (name "Net-(D7-A)") (class "Default")
      (node (ref "C20") (pin "2") (pinfunction "2_2") (pintype "passive"))
      (node (ref "D7") (pin "1") (pinfunction "A_1") (pintype "passive"))
      (node (ref "J9") (pin "1") (pinfunction "1_1") (pintype "passive"))
      (node (ref "Q8") (pin "C") (pinfunction "C_C") (pintype "passive"))
    )
    (net (code "74") (name "Net-(J6-Pad1)") (class "Default")
      (node (ref "J6") (pin "1") (pinfunction "1_1") (pintype "passive"))
      (node (ref "U7") (pin "5") (pinfunction "5_5") (pintype "passive"))
    )
    (net (code "75") (name "Net-(J6-Pad2)") (class "Default")
      (node (ref "J6") (pin "2") (pinfunction "2_2") (pintype "passive"))
      (node (ref "U7") (pin "7") (pinfunction "7_7") (pintype "passive"))
    )
    (net (code "76") (name "Net-(Q1-PadB)") (class "Default")
      (node (ref "Q1") (pin "B") (pinfunction "B_B") (pintype "passive"))
      (node (ref "R7") (pin "1") (pintype "passive"))
      (node (ref "R9") (pin "2") (pintype "passive"))
    )
    (net (code "77") (name "Net-(Q2-PadB)") (class "Default")
      (node (ref "Q2") (pin "B") (pinfunction "B_B") (pintype "passive"))
      (node (ref "R15") (pin "1") (pintype "passive"))
      (node (ref "R16") (pin "2") (pintype "passive"))
    )
    (net (code "78") (name "Net-(Q3-PadB)") (class "Default")
      (node (ref "Q3") (pin "B") (pinfunction "B_B") (pintype "passive"))
      (node (ref "R27") (pin "1") (pintype "passive"))
      (node (ref "R33") (pin "1") (pintype "passive"))
    )
    (net (code "79") (name "Net-(Q4-PadB)") (class "Default")
      (node (ref "Q4") (pin "B") (pinfunction "B_B") (pintype "passive"))
      (node (ref "R32") (pin "1") (pintype "passive"))
      (node (ref "R35") (pin "1") (pintype "passive"))
    )
    (net (code "80") (name "Net-(Q5-PadB)") (class "Default")
      (node (ref "Q5") (pin "B") (pinfunction "B_B") (pintype "passive"))
      (node (ref "R40") (pin "1") (pintype "passive"))
      (node (ref "R44") (pin "2") (pintype "passive"))
    )
    (net (code "81") (name "Net-(Q6-PadB)") (class "Default")
      (node (ref "Q6") (pin "B") (pinfunction "B_B") (pintype "passive"))
      (node (ref "R42") (pin "1") (pintype "passive"))
      (node (ref "R46") (pin "1") (pintype "passive"))
    )
    (net (code "82") (name "Net-(Q7-PadB)") (class "Default")
      (node (ref "Q7") (pin "B") (pinfunction "B_B") (pintype "passive"))
      (node (ref "R50") (pin "1") (pintype "passive"))
      (node (ref "R53") (pin "2") (pintype "passive"))
    )
    (net (code "83") (name "Net-(Q8-PadB)") (class "Default")
      (node (ref "Q8") (pin "B") (pinfunction "B_B") (pintype "passive"))
      (node (ref "R55") (pin "1") (pintype "passive"))
      (node (ref "R60") (pin "1") (pintype "passive"))
    )
    (net (code "84") (name "Net-(Q9-PadB)") (class "Default")
      (node (ref "Q9") (pin "B") (pinfunction "B_B") (pintype "passive"))
      (node (ref "R61") (pin "1") (pintype "passive"))
      (node (ref "R64") (pin "2") (pintype "passive"))
    )
    (net (code "85") (name "Net-(R1-Pad1)") (class "Default")
      (node (ref "R1") (pin "1") (pintype "passive"))
      (node (ref "U2") (pin "AC2") (pinfunction "～_AC2") (pintype "passive"))
    )
    (net (code "86") (name "Net-(R3-Pad1)") (class "Default")
      (node (ref "R3") (pin "1") (pintype "passive"))
      (node (ref "U2") (pin "AC1") (pinfunction "～_AC1") (pintype "passive"))
    )
    (net (code "87") (name "Net-(R4-Pad1)") (class "Default")
      (node (ref "R4") (pin "1") (pintype "passive"))
      (node (ref "R5") (pin "1") (pintype "passive"))
    )
    (net (code "88") (name "Net-(R8-Pad2)") (class "Default")
      (node (ref "R8") (pin "2") (pinfunction "2_2") (pintype "passive"))
      (node (ref "U4") (pin "16") (pinfunction "16_16") (pintype "passive"))
    )
    (net (code "89") (name "Net-(R12-Pad1)") (class "Default")
      (node (ref "R12") (pin "1") (pintype "passive"))
      (node (ref "R13") (pin "1") (pintype "passive"))
    )
    (net (code "90") (name "Net-(R17-Pad1)") (class "Default")
      (node (ref "R17") (pin "1") (pinfunction "1_1") (pintype "passive"))
      (node (ref "R20") (pin "2") (pinfunction "2_2") (pintype "passive"))
      (node (ref "U6") (pin "3") (pinfunction "3_3") (pintype "passive"))
    )
    (net (code "91") (name "Net-(R19-Pad2)") (class "Default")
      (node (ref "R19") (pin "2") (pinfunction "2_2") (pintype "passive"))
      (node (ref "U6") (pin "4") (pinfunction "4_4") (pintype "passive"))
    )
    (net (code "92") (name "Net-(R22-Pad2)") (class "Default")
      (node (ref "R22") (pin "2") (pinfunction "2_2") (pintype "passive"))
      (node (ref "U7") (pin "2") (pinfunction "2_2") (pintype "passive"))
    )
    (net (code "93") (name "Net-(R25-Pad2)") (class "Default")
      (node (ref "R25") (pin "2") (pinfunction "2_2") (pintype "passive"))
      (node (ref "U9") (pin "5") (pinfunction "5_5") (pintype "passive"))
    )
    (net (code "94") (name "Net-(R26-Pad1)") (class "Default")
      (node (ref "R26") (pin "1") (pinfunction "1_1") (pintype "passive"))
      (node (ref "R31") (pin "1") (pinfunction "1_1") (pintype "passive"))
      (node (ref "U10") (pin "14") (pinfunction "14_14") (pintype "passive"))
    )
    (net (code "95") (name "Net-(R26-Pad2)") (class "Default")
      (node (ref "R26") (pin "2") (pinfunction "2_2") (pintype "passive"))
      (node (ref "R34") (pin "1") (pinfunction "1_1") (pintype "passive"))
      (node (ref "U10") (pin "5") (pinfunction "5_5") (pintype "passive"))
    )
    (net (code "96") (name "Net-(R28-Pad2)") (class "Default")
      (node (ref "R28") (pin "2") (pinfunction "2_2") (pintype "passive"))
      (node (ref "R36") (pin "1") (pinfunction "1_1") (pintype "passive"))
      (node (ref "U10") (pin "3") (pinfunction "3_3") (pintype "passive"))
    )
    (net (code "97") (name "Net-(R29-Pad1)") (class "Default")
      (node (ref "R29") (pin "1") (pinfunction "1_1") (pintype "passive"))
      (node (ref "U10") (pin "2") (pinfunction "2_2") (pintype "passive"))
      (node (ref "U8") (pin "5") (pinfunction "5_5") (pintype "passive"))
    )
    (net (code "98") (name "Net-(R31-Pad2)") (class "Default")
      (node (ref "R31") (pin "2") (pinfunction "2_2") (pintype "passive"))
      (node (ref "R37") (pin "1") (pinfunction "1_1") (pintype "passive"))
      (node (ref "U10") (pin "13") (pinfunction "13_13") (pintype "passive"))
    )
    (net (code "99") (name "Net-(R37-Pad2)") (class "Default")
      (node (ref "R37") (pin "2") (pinfunction "2_2") (pintype "passive"))
      (node (ref "R41") (pin "2") (pinfunction "2_2") (pintype "passive"))
      (node (ref "U10") (pin "9") (pinfunction "9_9") (pintype "passive"))
    )
    (net (code "100") (name "Net-(R39-Pad1)") (class "Default")
      (node (ref "R39") (pin "1") (pinfunction "1_1") (pintype "passive"))
      (node (ref "R43") (pin "2") (pinfunction "2_2") (pintype "passive"))
      (node (ref "U10") (pin "6") (pinfunction "6_6") (pintype "passive"))
    )
    (net (code "101") (name "Net-(R39-Pad2)") (class "Default")
      (node (ref "R39") (pin "2") (pinfunction "2_2") (pintype "passive"))
      (node (ref "R45") (pin "2") (pinfunction "2_2") (pintype "passive"))
      (node (ref "U10") (pin "7") (pinfunction "7_7") (pintype "passive"))
    )
    (net (code "102") (name "Net-(R41-Pad1)") (class "Default")
      (node (ref "R41") (pin "1") (pinfunction "1_1") (pintype "passive"))
      (node (ref "R43") (pin "1") (pinfunction "1_1") (pintype "passive"))
      (node (ref "U10") (pin "8") (pinfunction "8_8") (pintype "passive"))
    )
    (net (code "103") (name "Net-(R47-Pad1)") (class "Default")
      (node (ref "R47") (pin "1") (pinfunction "1_1") (pintype "passive"))
      (node (ref "R52") (pin "1") (pinfunction "1_1") (pintype "passive"))
      (node (ref "U13") (pin "14") (pinfunction "14_14") (pintype "passive"))
    )
    (net (code "104") (name "Net-(R47-Pad2)") (class "Default")
      (node (ref "R47") (pin "2") (pinfunction "2_2") (pintype "passive"))
      (node (ref "R54") (pin "1") (pinfunction "1_1") (pintype "passive"))
      (node (ref "U13") (pin "5") (pinfunction "5_5") (pintype "passive"))
    )
    (net (code "105") (name "Net-(R48-Pad2)") (class "Default")
      (node (ref "R48") (pin "2") (pinfunction "2_2") (pintype "passive"))
      (node (ref "R56") (pin "1") (pinfunction "1_1") (pintype "passive"))
      (node (ref "U13") (pin "3") (pinfunction "3_3") (pintype "passive"))
    )
    (net (code "106") (name "Net-(R49-Pad1)") (class "Default")
      (node (ref "R49") (pin "1") (pinfunction "1_1") (pintype "passive"))
      (node (ref "U11") (pin "5") (pinfunction "5_5") (pintype "passive"))
      (node (ref "U13") (pin "2") (pinfunction "2_2") (pintype "passive"))
    )
    (net (code "107") (name "Net-(R52-Pad2)") (class "Default")
      (node (ref "R52") (pin "2") (pinfunction "2_2") (pintype "passive"))
      (node (ref "R57") (pin "1") (pinfunction "1_1") (pintype "passive"))
      (node (ref "U13") (pin "13") (pinfunction "13_13") (pintype "passive"))
    )
    (net (code "108") (name "Net-(R57-Pad2)") (class "Default")
      (node (ref "R57") (pin "2") (pinfunction "2_2") (pintype "passive"))
      (node (ref "R62") (pin "2") (pinfunction "2_2") (pintype "passive"))
      (node (ref "U13") (pin "9") (pinfunction "9_9") (pintype "passive"))
    )
    (net (code "109") (name "Net-(R59-Pad1)") (class "Default")
      (node (ref "R59") (pin "1") (pinfunction "1_1") (pintype "passive"))
      (node (ref "R63") (pin "2") (pinfunction "2_2") (pintype "passive"))
      (node (ref "U13") (pin "6") (pinfunction "6_6") (pintype "passive"))
    )
    (net (code "110") (name "Net-(R59-Pad2)") (class "Default")
      (node (ref "R59") (pin "2") (pinfunction "2_2") (pintype "passive"))
      (node (ref "R65") (pin "2") (pinfunction "2_2") (pintype "passive"))
      (node (ref "U13") (pin "7") (pinfunction "7_7") (pintype "passive"))
    )
    (net (code "111") (name "Net-(R62-Pad1)") (class "Default")
      (node (ref "R62") (pin "1") (pinfunction "1_1") (pintype "passive"))
      (node (ref "R63") (pin "1") (pinfunction "1_1") (pintype "passive"))
      (node (ref "U13") (pin "8") (pinfunction "8_8") (pintype "passive"))
    )
    (net (code "112") (name "Net-(R68-Pad2)") (class "Default")
      (node (ref "R68") (pin "2") (pinfunction "2_2") (pintype "passive"))
      (node (ref "U7") (pin "1") (pinfunction "1_1") (pintype "passive"))
    )
    (net (code "113") (name "Net-(U1-AN)") (class "Default")
      (node (ref "U1") (pin "1") (pinfunction "AN_1") (pintype "passive"))
      (node (ref "U2") (pin "V+") (pinfunction "+_V+") (pintype "passive"))
    )
    (net (code "114") (name "Net-(U1-CAT)") (class "Default")
      (node (ref "U1") (pin "2") (pinfunction "CAT_2") (pintype "passive"))
      (node (ref "U2") (pin "V-") (pinfunction "-_V-") (pintype "passive"))
    )
    (net (code "115") (name "Net-(U3-A)") (class "Default")
      (node (ref "R6") (pin "2") (pintype "passive"))
      (node (ref "U3") (pin "1") (pinfunction "A_1") (pintype "passive"))
    )
    (net (code "116") (name "Net-(U3-C)") (class "Default")
      (node (ref "Q1") (pin "C") (pinfunction "C_C") (pintype "passive"))
      (node (ref "U3") (pin "2") (pinfunction "C_2") (pintype "passive"))
    )
    (net (code "117") (name "Net-(U3-MT1)") (class "Default")
      (node (ref "R5") (pin "2") (pintype "passive"))
      (node (ref "U3") (pin "6") (pinfunction "MT1_6") (pintype "passive"))
    )
    (net (code "118") (name "Net-(U3-MT2)") (class "Default")
      (node (ref "TR1") (pin "3") (pintype "passive"))
      (node (ref "U3") (pin "4") (pinfunction "MT2_4") (pintype "passive"))
    )
    (net (code "119") (name "Net-(U5-A)") (class "Default")
      (node (ref "R14") (pin "2") (pintype "passive"))
      (node (ref "U5") (pin "1") (pinfunction "A_1") (pintype "passive"))
    )
    (net (code "120") (name "Net-(U5-C)") (class "Default")
      (node (ref "Q2") (pin "C") (pinfunction "C_C") (pintype "passive"))
      (node (ref "U5") (pin "2") (pinfunction "C_2") (pintype "passive"))
    )
    (net (code "121") (name "Net-(U5-MT1)") (class "Default")
      (node (ref "R12") (pin "2") (pintype "passive"))
      (node (ref "U5") (pin "6") (pinfunction "MT1_6") (pintype "passive"))
    )
    (net (code "122") (name "Net-(U5-MT2)") (class "Default")
      (node (ref "TR2") (pin "3") (pintype "passive"))
      (node (ref "U5") (pin "4") (pinfunction "MT2_4") (pintype "passive"))
    )
    (net (code "123") (name "Net-(U10-Pad10)") (class "Default")
      (node (ref "U10") (pin "10") (pinfunction "10_10") (pintype "passive"))
      (node (ref "U8") (pin "1") (pinfunction "1_1") (pintype "passive"))
      (node (ref "U8") (pin "6") (pinfunction "6_6") (pintype "passive"))
    )
    (net (code "124") (name "Net-(U10-Pad12)") (class "Default")
      (node (ref "U10") (pin "12") (pinfunction "12_12") (pintype "passive"))
      (node (ref "U8") (pin "3") (pinfunction "3_3") (pintype "passive"))
    )
    (net (code "125") (name "Net-(U11-Pad1)") (class "Default")
      (node (ref "U11") (pin "1") (pinfunction "1_1") (pintype "passive"))
      (node (ref "U11") (pin "6") (pinfunction "6_6") (pintype "passive"))
      (node (ref "U13") (pin "10") (pinfunction "10_10") (pintype "passive"))
    )
    (net (code "126") (name "Net-(U11-Pad3)") (class "Default")
      (node (ref "U11") (pin "3") (pinfunction "3_3") (pintype "passive"))
      (node (ref "U13") (pin "12") (pinfunction "12_12") (pintype "passive"))
    )
    (net (code "127") (name "Net-(Y1-OSC1)") (class "Default")
      (node (ref "U9") (pin "8") (pinfunction "8_8") (pintype "passive"))
      (node (ref "Y1") (pin "1") (pinfunction "OSC1_1") (pintype "passive"))
    )
    (net (code "128") (name "unconnected-(LED9-dp-Pad7)") (class "Default")
      (node (ref "LED9") (pin "7") (pinfunction "dp_7") (pintype "passive"))
    )
    (net (code "129") (name "unconnected-(U3-NC-Pad3)") (class "Default")
      (node (ref "U3") (pin "3") (pinfunction "NC_3") (pintype "passive+no_connect"))
    )
    (net (code "130") (name "unconnected-(U3-SBU-Pad5)") (class "Default")
      (node (ref "U3") (pin "5") (pinfunction "SBU_5") (pintype "passive+no_connect"))
    )
    (net (code "131") (name "unconnected-(U4-Pad9)") (class "Default")
      (node (ref "U4") (pin "9") (pinfunction "9_9") (pintype "passive"))
    )
    (net (code "132") (name "unconnected-(U5-NC-Pad3)") (class "Default")
      (node (ref "U5") (pin "3") (pinfunction "NC_3") (pintype "passive+no_connect"))
    )
    (net (code "133") (name "unconnected-(U5-SBU-Pad5)") (class "Default")
      (node (ref "U5") (pin "5") (pinfunction "SBU_5") (pintype "passive+no_connect"))
    )
    (net (code "134") (name "unconnected-(U7-Pad3)") (class "Default")
      (node (ref "U7") (pin "3") (pinfunction "3_3") (pintype "passive"))
    )
    (net (code "135") (name "unconnected-(U7-Pad4)") (class "Default")
      (node (ref "U7") (pin "4") (pinfunction "4_4") (pintype "passive"))
    )
    (net (code "136") (name "unconnected-(U8-Pad4)") (class "Default")
      (node (ref "U8") (pin "4") (pinfunction "4_4") (pintype "passive+no_connect"))
    )
    (net (code "137") (name "unconnected-(U9-Pad7)") (class "Default")
      (node (ref "U9") (pin "7") (pinfunction "7_7") (pintype "passive+no_connect"))
    )
    (net (code "138") (name "unconnected-(U11-Pad4)") (class "Default")
      (node (ref "U11") (pin "4") (pinfunction "4_4") (pintype "passive+no_connect"))
    )
    (net (code "139") (name "unconnected-(U12-Pad1)") (class "Default")
      (node (ref "U12") (pin "1") (pinfunction "1_1") (pintype "passive"))
    )
    (net (code "140") (name "unconnected-(U12-Pad3)") (class "Default")
      (node (ref "U12") (pin "3") (pinfunction "3_3") (pintype "passive"))
    )
    (net (code "141") (name "unconnected-(U12-Pad13)") (class "Default")
      (node (ref "U12") (pin "13") (pinfunction "13_13") (pintype "passive"))
    )
    (net (code "142") (name "unconnected-(U12-Pad16)") (class "Default")
      (node (ref "U12") (pin "16") (pinfunction "16_16") (pintype "passive"))
    )
    (net (code "143") (name "unconnected-(U12-Pad22)") (class "Default")
      (node (ref "U12") (pin "22") (pinfunction "22_22") (pintype "passive"))
    )
    (net (code "144") (name "unconnected-(U12-Pad23)") (class "Default")
      (node (ref "U12") (pin "23") (pinfunction "23_23") (pintype "passive"))
    )
    (net (code "145") (name "unconnected-(U12-Pad24)") (class "Default")
      (node (ref "U12") (pin "24") (pinfunction "24_24") (pintype "passive"))
    )
    (net (code "146") (name "unconnected-(U12-Pad27)") (class "Default")
      (node (ref "U12") (pin "27") (pinfunction "27_27") (pintype "passive"))
    )
    (net (code "147") (name "unconnected-(U12-Pad32)") (class "Default")
      (node (ref "U12") (pin "32") (pinfunction "32_32") (pintype "passive"))
    )
  )
)
